# Speaker-Amplifier.net
KiCad netlist of a schematic drawn in Altium Designer
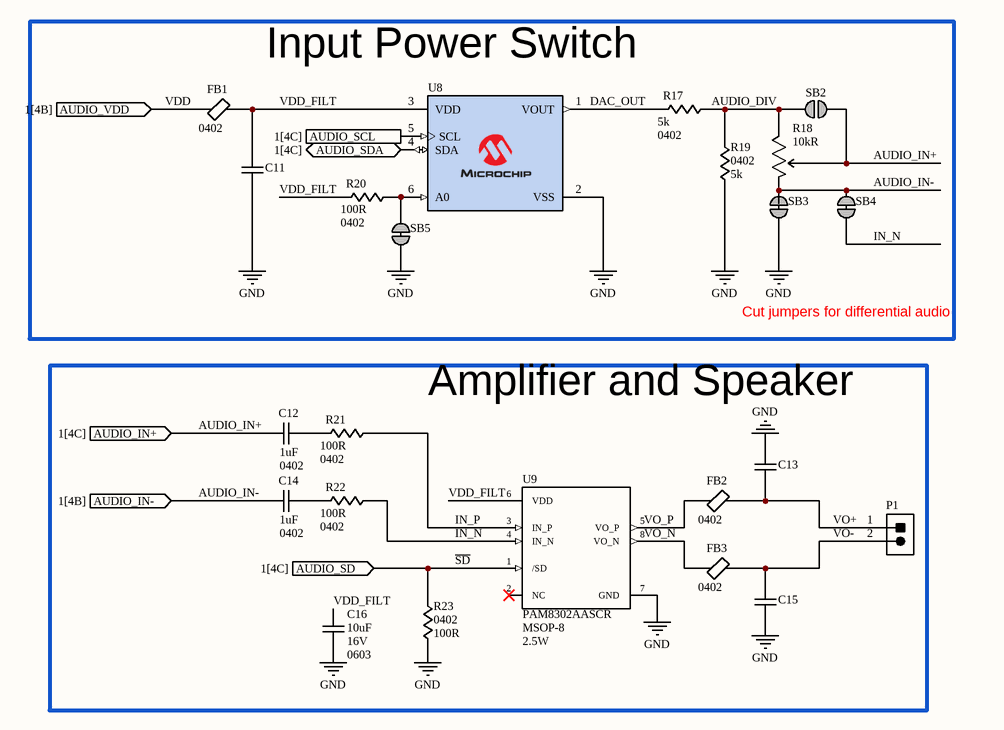
[diagram p0: Speaker-Amplifier.SchDoc]

(export (version "E")
  (design (tool "Eeschema 10.0.6"))
  (components
    (comp (ref "C11")
      (value "CAP-SMD-0402")
      (footprint "PCB-CAP-SMD-0402")
      (description "Generic (no part number) 0402 surface mount capacitor")
      (libsource (lib "Animal Inspired Movement and Robotics Lab (AIMRL)") (part "SCH-CAP-SMD-0402"))
    )
    (comp (ref "C12")
      (value "1uF")
      (footprint "PCB-CAP-SMD-0402")
      (description "Generic (no part number) 0402 surface mount capacitor")
      (fields (field (name "VOLTAGE") "0402") (field (name "Comment") "CAP-SMD-0402"))
      (libsource (lib "Animal Inspired Movement and Robotics Lab (AIMRL)") (part "SCH-CAP-SMD-0402"))
    )
    (comp (ref "C13")
      (value "CAP-SMD-0402")
      (footprint "PCB-CAP-SMD-0402")
      (description "Generic (no part number) 0402 surface mount capacitor")
      (libsource (lib "Animal Inspired Movement and Robotics Lab (AIMRL)") (part "SCH-CAP-SMD-0402"))
    )
    (comp (ref "C14")
      (value "1uF")
      (footprint "PCB-CAP-SMD-0402")
      (description "Generic (no part number) 0402 surface mount capacitor")
      (fields (field (name "VOLTAGE") "0402") (field (name "Comment") "CAP-SMD-0402"))
      (libsource (lib "Animal Inspired Movement and Robotics Lab (AIMRL)") (part "SCH-CAP-SMD-0402"))
    )
    (comp (ref "C15")
      (value "CAP-SMD-0402")
      (footprint "PCB-CAP-SMD-0402")
      (description "Generic (no part number) 0402 surface mount capacitor")
      (libsource (lib "Animal Inspired Movement and Robotics Lab (AIMRL)") (part "SCH-CAP-SMD-0402"))
    )
    (comp (ref "C16")
      (value "10uF")
      (footprint "0603")
      (description "Generic (no part number) 0603 surface mount capacitor")
      (fields (field (name "VOLTAGE") "16V") (field (name "Comment") "CAP-SMD-0603"))
      (libsource (lib "Animal Inspired Movement and Robotics Lab (AIMRL)") (part "SCH-CAP-SMD-0603"))
    )
    (comp (ref "FB1")
      (value "FERRITE-SMD-GENERIC-0402")
      (footprint "0402")
      (description "Generic (no part number) 0402 ferrite bead")
      (libsource (lib "Animal Inspired Movement and Robotics Lab (AIMRL)") (part "SCH-FERRITE-BEAD"))
    )
    (comp (ref "FB2")
      (value "FERRITE-SMD-GENERIC-0402")
      (footprint "0402")
      (description "Generic (no part number) 0402 ferrite bead")
      (libsource (lib "Animal Inspired Movement and Robotics Lab (AIMRL)") (part "SCH-FERRITE-BEAD"))
    )
    (comp (ref "FB3")
      (value "FERRITE-SMD-GENERIC-0402")
      (footprint "0402")
      (description "Generic (no part number) 0402 ferrite bead")
      (libsource (lib "Animal Inspired Movement and Robotics Lab (AIMRL)") (part "SCH-FERRITE-BEAD"))
    )
    (comp (ref "P1")
      (value "CONN-PICOBLADE-SMD-1.25MM-2PIN-53261-0271")
      (footprint "PCB-PICOBLADE-2PIN-1.25MM")
      (description "1.25mm Pitch PicoBlade™ Header, Surface Mount, Right Angle, Lead-Free, 2 Circuits")
      (libsource (lib "Animal Inspired Movement and Robotics Lab (AIMRL)") (part "SCH-SMD-CONN-2PIN-2MT"))
    )
    (comp (ref "R17")
      (value "5k")
      (footprint "0402")
      (description "Generic (no part number) 0402 surface mount resistor")
      (fields (field (name "Comment") "RES-SMD-0402"))
      (libsource (lib "Animal Inspired Movement and Robotics Lab (AIMRL)") (part "SCH-RES-SMA-0402"))
    )
    (comp (ref "R18")
      (value "10kR")
      (footprint "PCB-FP-3352T-MFG")
      (description "Trimmer Potentiometer 10k Ohm 20% 1/2 Watt 1 Turn Pin Through Hole")
      (fields (field (name "TOLERANCE") "20%") (field (name "Comment") "POT-THUMB-9MM-3352T-1-103LF"))
      (libsource (lib "Animal Inspired Movement and Robotics Lab (AIMRL)") (part "SCH-POTENTIOMETER"))
    )
    (comp (ref "R19")
      (value "5k")
      (footprint "0402")
      (description "Generic (no part number) 0402 surface mount resistor")
      (fields (field (name "Comment") "RES-SMD-0402"))
      (libsource (lib "Animal Inspired Movement and Robotics Lab (AIMRL)") (part "SCH-RES-SMA-0402"))
    )
    (comp (ref "R20")
      (value "100R")
      (footprint "0402")
      (description "Generic (no part number) 0402 surface mount resistor")
      (fields (field (name "Comment") "RES-SMD-0402"))
      (libsource (lib "Animal Inspired Movement and Robotics Lab (AIMRL)") (part "SCH-RES-SMA-0402"))
    )
    (comp (ref "R21")
      (value "100R")
      (footprint "0402")
      (description "Generic (no part number) 0402 surface mount resistor")
      (fields (field (name "Comment") "RES-SMD-0402"))
      (libsource (lib "Animal Inspired Movement and Robotics Lab (AIMRL)") (part "SCH-RES-SMA-0402"))
    )
    (comp (ref "R22")
      (value "100R")
      (footprint "0402")
      (description "Generic (no part number) 0402 surface mount resistor")
      (fields (field (name "Comment") "RES-SMD-0402"))
      (libsource (lib "Animal Inspired Movement and Robotics Lab (AIMRL)") (part "SCH-RES-SMA-0402"))
    )
    (comp (ref "R23")
      (value "100R")
      (footprint "0402")
      (description "Generic (no part number) 0402 surface mount resistor")
      (fields (field (name "Comment") "RES-SMD-0402"))
      (libsource (lib "Animal Inspired Movement and Robotics Lab (AIMRL)") (part "SCH-RES-SMA-0402"))
    )
    (comp (ref "SB2")
      (value "SB-OPEN-NO-PASTE")
      (footprint "PCB-SOLDERJUMPER-NOPASTE")
      (description "Solder bridge, normally open, no solder paste.")
      (libsource (lib "Animal Inspired Movement and Robotics Lab (AIMRL)") (part "SCH-SOLDERBRIDGE-OPEN"))
    )
    (comp (ref "SB3")
      (value "SB-CLOSED-NO-PASTE")
      (footprint "-SOLDERJUMPER-CLOSEDWIRE")
      (description "Solder bridge, normally closed")
      (libsource (lib "Animal Inspired Movement and Robotics Lab (AIMRL)") (part "SCH-SOLDERBRIDGE-SHORTED"))
    )
    (comp (ref "SB4")
      (value "SB-CLOSED-NO-PASTE")
      (footprint "-SOLDERJUMPER-CLOSEDWIRE")
      (description "Solder bridge, normally closed")
      (libsource (lib "Animal Inspired Movement and Robotics Lab (AIMRL)") (part "SCH-SOLDERBRIDGE-SHORTED"))
    )
    (comp (ref "SB5")
      (value "SB-CLOSED-NO-PASTE")
      (footprint "-SOLDERJUMPER-CLOSEDWIRE")
      (description "Solder bridge, normally closed")
      (libsource (lib "Animal Inspired Movement and Robotics Lab (AIMRL)") (part "SCH-SOLDERBRIDGE-SHORTED"))
    )
    (comp (ref "U8")
      (value "IC-DAC-12BIT-1CH-I2C-MCP4725A0T-E/CH")
      (footprint "PCB-MCP4725-MSOP-10-3X3MM")
      (description "IC DAC 12BIT W/I2C SOT23A-6")
      (libsource (lib "Animal Inspired Movement and Robotics Lab (AIMRL)") (part "SCH-MCP4725AOT-E/CH"))
    )
    (comp (ref "U9")
      (value "IC-AUDIO-AMP-2.5W-PAM8302AASCR")
      (footprint "PCB-MSOP-8-.65MM")
      (description "IC AMP AUDIO 2.5W CLASS D 8MSOP")
      (fields
        (field (name "CASE/PACKAGE") "MSOP-8")
        (field (name "OUTPUT POWER") "2.5W")
        (field (name "PART NUMBER") "PAM8302AASCR")
      )
      (libsource (lib "Animal Inspired Movement and Robotics Lab (AIMRL)") (part "SCH-AUDIO-AMP-PAM8302A"))
    )
  )
  (nets
    (net (code "1") (name "/AUDIO_DIV") (class "Default")
      (node (ref "R17") (pin "2") (pinfunction "2_2") (pintype "passive"))
      (node (ref "R18") (pin "1") (pinfunction "CCW_1") (pintype "passive"))
      (node (ref "R19") (pin "1") (pinfunction "1_1") (pintype "passive"))
      (node (ref "SB2") (pin "2") (pinfunction "1_2") (pintype "passive"))
    )
    (net (code "2") (name "/AUDIO_IN+") (class "Default")
      (node (ref "C12") (pin "1") (pinfunction "1_1") (pintype "passive"))
      (node (ref "R18") (pin "2") (pinfunction "WIPER_2") (pintype "passive"))
      (node (ref "SB2") (pin "1") (pinfunction "0_1") (pintype "passive"))
    )
    (net (code "3") (name "/AUDIO_IN-") (class "Default")
      (node (ref "C14") (pin "1") (pinfunction "1_1") (pintype "passive"))
      (node (ref "R18") (pin "3") (pinfunction "CW_3") (pintype "passive"))
      (node (ref "SB3") (pin "1") (pinfunction "0_1") (pintype "passive"))
      (node (ref "SB4") (pin "1") (pinfunction "0_1") (pintype "passive"))
    )
    (net (code "4") (name "/AUDIO_SCL") (class "Default")
      (node (ref "U8") (pin "5") (pinfunction "SCL_5") (pintype "input"))
    )
    (net (code "5") (name "/AUDIO_SDA") (class "Default")
      (node (ref "U8") (pin "4") (pinfunction "SDA_4") (pintype "bidirectional"))
    )
    (net (code "6") (name "/DAC_OUT") (class "Default")
      (node (ref "R17") (pin "1") (pinfunction "1_1") (pintype "passive"))
      (node (ref "U8") (pin "1") (pinfunction "VOUT_1") (pintype "output"))
    )
    (net (code "7") (name "/IN_N") (class "Default")
      (node (ref "R22") (pin "2") (pinfunction "2_2") (pintype "passive"))
      (node (ref "SB4") (pin "2") (pinfunction "1_2") (pintype "passive"))
      (node (ref "U9") (pin "4") (pinfunction "IN_N_4") (pintype "input"))
    )
    (net (code "8") (name "/IN_P") (class "Default")
      (node (ref "R21") (pin "2") (pinfunction "2_2") (pintype "passive"))
      (node (ref "U9") (pin "3") (pinfunction "IN_P_3") (pintype "input"))
    )
    (net (code "9") (name "/VDD") (class "Default")
      (node (ref "FB1") (pin "1") (pinfunction "1_1") (pintype "passive"))
    )
    (net (code "10") (name "/VDD_FILT") (class "Default")
      (node (ref "C11") (pin "2") (pinfunction "2_2") (pintype "passive"))
      (node (ref "C16") (pin "2") (pinfunction "2_2") (pintype "passive"))
      (node (ref "FB1") (pin "2") (pinfunction "2_2") (pintype "passive"))
      (node (ref "R20") (pin "1") (pinfunction "1_1") (pintype "passive"))
      (node (ref "U8") (pin "3") (pinfunction "VDD_3") (pintype "power_in"))
      (node (ref "U9") (pin "6") (pinfunction "VDD_6") (pintype "power_in"))
    )
    (net (code "11") (name "/VO+") (class "Default")
      (node (ref "C13") (pin "1") (pinfunction "1_1") (pintype "passive"))
      (node (ref "FB2") (pin "2") (pinfunction "2_2") (pintype "passive"))
      (node (ref "P1") (pin "1") (pinfunction "1_1") (pintype "passive"))
    )
    (net (code "12") (name "/VO-") (class "Default")
      (node (ref "C15") (pin "2") (pinfunction "2_2") (pintype "passive"))
      (node (ref "FB3") (pin "2") (pinfunction "2_2") (pintype "passive"))
      (node (ref "P1") (pin "2") (pinfunction "2_2") (pintype "passive"))
    )
    (net (code "13") (name "/VO_N") (class "Default")
      (node (ref "FB3") (pin "1") (pinfunction "1_1") (pintype "passive"))
      (node (ref "U9") (pin "8") (pinfunction "VO_N_8") (pintype "output"))
    )
    (net (code "14") (name "/VO_P") (class "Default")
      (node (ref "FB2") (pin "1") (pinfunction "1_1") (pintype "passive"))
      (node (ref "U9") (pin "5") (pinfunction "VO_P_5") (pintype "output"))
    )
    (net (code "15") (name "/~{SD}") (class "Default")
      (node (ref "R23") (pin "2") (pinfunction "2_2") (pintype "passive"))
      (node (ref "U9") (pin "1") (pinfunction "/SD_1") (pintype "input"))
    )
    (net (code "16") (name "GND") (class "Default")
      (node (ref "C11") (pin "1") (pinfunction "1_1") (pintype "passive"))
      (node (ref "C13") (pin "2") (pinfunction "2_2") (pintype "passive"))
      (node (ref "C15") (pin "1") (pinfunction "1_1") (pintype "passive"))
      (node (ref "C16") (pin "1") (pinfunction "1_1") (pintype "passive"))
      (node (ref "R19") (pin "2") (pinfunction "2_2") (pintype "passive"))
      (node (ref "R23") (pin "1") (pinfunction "1_1") (pintype "passive"))
      (node (ref "SB3") (pin "2") (pinfunction "1_2") (pintype "passive"))
      (node (ref "SB5") (pin "2") (pinfunction "1_2") (pintype "passive"))
      (node (ref "U8") (pin "2") (pinfunction "VSS_2") (pintype "power_in"))
      (node (ref "U9") (pin "7") (pinfunction "GND_7") (pintype "power_in"))
    )
    (net (code "17") (name "Net-(C12-Pad2)") (class "Default")
      (node (ref "C12") (pin "2") (pinfunction "2_2") (pintype "passive"))
      (node (ref "R21") (pin "1") (pinfunction "1_1") (pintype "passive"))
    )
    (net (code "18") (name "Net-(C14-Pad2)") (class "Default")
      (node (ref "C14") (pin "2") (pinfunction "2_2") (pintype "passive"))
      (node (ref "R22") (pin "1") (pinfunction "1_1") (pintype "passive"))
    )
    (net (code "19") (name "Net-(P1-PadMP1)") (class "Default")
      (node (ref "P1") (pin "MP1") (pinfunction "MP1_MP1") (pintype "passive"))
      (node (ref "P1") (pin "MP2") (pinfunction "MP2_MP2") (pintype "passive"))
    )
    (net (code "20") (name "Net-(SB5-0)") (class "Default")
      (node (ref "R20") (pin "2") (pinfunction "2_2") (pintype "passive"))
      (node (ref "SB5") (pin "1") (pinfunction "0_1") (pintype "passive"))
      (node (ref "U8") (pin "6") (pinfunction "A0_6") (pintype "input"))
    )
    (net (code "21") (name "unconnected-(U9-NC-Pad2)") (class "Default")
      (node (ref "U9") (pin "2") (pinfunction "NC_2") (pintype "passive+no_connect"))
    )
  )
)
